# Servos.net
KiCad netlist of a schematic drawn in Altium Designer
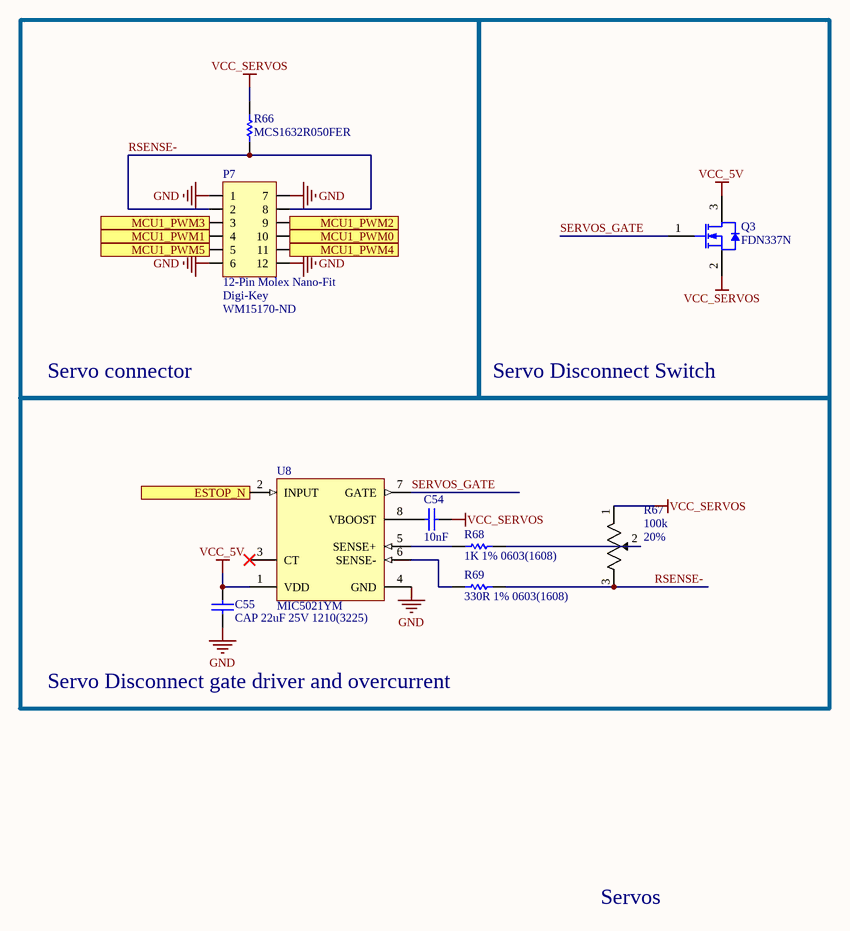
[diagram p0: Servos.SchDoc]

(export (version "E")
  (design (tool "Eeschema 10.0.6"))
  (components
    (comp (ref "C54")
      (value "10nF")
      (footprint "CAPC0603(1608)100_N")
      (description "CAP 10nF 25V ±2% 0603 (1608 Metric) Thickness 1mm SMD")
      (fields (field (name "TOLERANCE") "Â±2%"))
      (libsource (lib "Altium Content Vault") (part "CAP"))
    )
    (comp (ref "C55")
      (value "CAP 22uF 25V 1210(3225)")
      (footprint "CAPC1210(3225)220_N")
      (description "CAP 22uF 25V -20% to +80% 1210 (3225 Metric) Thickness 2.2mm SMD")
      (fields (field (name "TOLERANCE") "-20% to +80%"))
      (libsource (lib "Altium Content Vault") (part "CAP"))
    )
    (comp (ref "P7")
      (value "12-Pin Molex Nano-Fit")
      (footprint "MOLEX NANO-FIT 2X6 - Right Angle")
      (description "NanoFit RA Hdr TH DR 12Ckt")
      (fields (field (name "SUPPLIER 1") "Digi-Key") (field (name "SUPPLIER PART NUMBER 1") "WM15170-ND"))
      (libsource (lib "CMR_Connectors") (part "12-Pin 2-Row Nano-Fit"))
    )
    (comp (ref "Q3")
      (value "FDN337N")
      (footprint "FAIR-SSOT3L-3_V")
      (fields (field (name "MANUFACTURER") "Fairchild Semiconductor"))
      (libsource (lib "Altium Content Vault") (part "NEMOS-GSD-3"))
    )
    (comp (ref "R66")
      (value "MCS1632R050FER")
      (footprint "RESC3216X62X50LL20T20")
      (description "Chip Resistor, 0.05 Ohm, +/- 1%, 1 W, -55 to 155 degC, 1206 (3216 Metric), RoHS, Tape and Reel")
      (fields (field (name "TOLERANCE") "50ppm"))
      (libsource (lib "Altium Content Vault") (part "RES-2"))
    )
    (comp (ref "R67")
      (value "100k")
      (footprint "TT BI 22A TRIM POT")
      (description "TT Electronics BI 22AR100KLFTR SMT trim pot, 100k 20%")
      (fields (field (name "TOLERANCE") "20%") (field (name "Comment") "22AR100KLFTR"))
      (libsource (lib "CMR_Resistors_Capacitors_and_Inductors") (part "TT 22AR Trim Pot"))
    )
    (comp (ref "R68")
      (value "1K 1% 0603(1608)")
      (footprint "RESC0603(1608)_N")
      (description "1K 0.1W 1% 0603 (1608 Metric)  SMD")
      (fields (field (name "TOLERANCE") "1 %") (field (name "POWER") "0.1 W"))
      (libsource (lib "Altium Content Vault") (part "RES"))
    )
    (comp (ref "R69")
      (value "330R 1% 0603(1608)")
      (footprint "RESC0603(1608)_N")
      (description "330R 0.1W 1% 0603 (1608 Metric)  SMD")
      (fields (field (name "TOLERANCE") "1 %") (field (name "POWER") "0.1 W"))
      (libsource (lib "Altium Content Vault") (part "RES"))
    )
    (comp (ref "U8")
      (value "MIC5021YM")
      (footprint "MICL-SOICN-8LD-PL-1_V")
      (description "High-Speed High-Side MOSFET Driver, 12 to 36 V, -40 to 85 degC, 8-Pin SOIC, RoHS, Tube")
      (libsource (lib "Altium Content Vault") (part "MICL-MIC5021B_YM-8"))
    )
  )
  (nets
    (net (code "1") (name "/ESTOP_N") (class "Default")
      (node (ref "U8") (pin "2") (pinfunction "INPUT_2") (pintype "input"))
    )
    (net (code "2") (name "/MCU1_PWM0") (class "Default")
      (node (ref "P7") (pin "10") (pinfunction "10_10") (pintype "passive"))
    )
    (net (code "3") (name "/MCU1_PWM1") (class "Default")
      (node (ref "P7") (pin "4") (pinfunction "4_4") (pintype "passive"))
    )
    (net (code "4") (name "/MCU1_PWM2") (class "Default")
      (node (ref "P7") (pin "9") (pinfunction "9_9") (pintype "passive"))
    )
    (net (code "5") (name "/MCU1_PWM3") (class "Default")
      (node (ref "P7") (pin "3") (pinfunction "3_3") (pintype "passive"))
    )
    (net (code "6") (name "/MCU1_PWM4") (class "Default")
      (node (ref "P7") (pin "11") (pinfunction "11_11") (pintype "passive"))
    )
    (net (code "7") (name "/MCU1_PWM5") (class "Default")
      (node (ref "P7") (pin "5") (pinfunction "5_5") (pintype "passive"))
    )
    (net (code "8") (name "/RSENSE-") (class "Default")
      (node (ref "P7") (pin "2") (pinfunction "2_2") (pintype "passive"))
      (node (ref "P7") (pin "8") (pinfunction "8_8") (pintype "passive"))
      (node (ref "R66") (pin "1") (pinfunction "1_1") (pintype "passive"))
      (node (ref "R67") (pin "3") (pinfunction "3_3") (pintype "passive"))
      (node (ref "R69") (pin "2") (pinfunction "2_2") (pintype "passive"))
    )
    (net (code "9") (name "/SERVOS_GATE") (class "Default")
      (node (ref "Q3") (pin "1") (pinfunction "G_1") (pintype "passive"))
      (node (ref "U8") (pin "7") (pinfunction "GATE_7") (pintype "output"))
    )
    (net (code "10") (name "GND") (class "Default")
      (node (ref "C55") (pin "1") (pinfunction "1_1") (pintype "passive"))
      (node (ref "P7") (pin "1") (pinfunction "1_1") (pintype "passive"))
      (node (ref "P7") (pin "12") (pinfunction "12_12") (pintype "passive"))
      (node (ref "P7") (pin "6") (pinfunction "6_6") (pintype "passive"))
      (node (ref "P7") (pin "7") (pinfunction "7_7") (pintype "passive"))
      (node (ref "U8") (pin "4") (pinfunction "GND_4") (pintype "power_in"))
    )
    (net (code "11") (name "Net-(R67-Pad2)") (class "Default")
      (node (ref "R67") (pin "2") (pinfunction "2_2") (pintype "passive"))
      (node (ref "R68") (pin "2") (pinfunction "2_2") (pintype "passive"))
    )
    (net (code "12") (name "Net-(U8-SENSE+)") (class "Default")
      (node (ref "R68") (pin "1") (pinfunction "1_1") (pintype "passive"))
      (node (ref "U8") (pin "5") (pinfunction "SENSE+_5") (pintype "input"))
    )
    (net (code "13") (name "Net-(U8-SENSE-)") (class "Default")
      (node (ref "R69") (pin "1") (pinfunction "1_1") (pintype "passive"))
      (node (ref "U8") (pin "6") (pinfunction "SENSE-_6") (pintype "input"))
    )
    (net (code "14") (name "Net-(U8-VBOOST)") (class "Default")
      (node (ref "C54") (pin "1") (pinfunction "1_1") (pintype "passive"))
      (node (ref "U8") (pin "8") (pinfunction "VBOOST_8") (pintype "power_in"))
    )
    (net (code "15") (name "VCC_5V") (class "Default")
      (node (ref "C55") (pin "2") (pinfunction "2_2") (pintype "passive"))
      (node (ref "Q3") (pin "3") (pinfunction "D_3") (pintype "passive"))
      (node (ref "U8") (pin "1") (pinfunction "VDD_1") (pintype "power_in"))
    )
    (net (code "16") (name "VCC_SERVOS") (class "Default")
      (node (ref "C54") (pin "2") (pinfunction "2_2") (pintype "passive"))
      (node (ref "Q3") (pin "2") (pinfunction "S_2") (pintype "passive"))
      (node (ref "R66") (pin "2") (pinfunction "2_2") (pintype "passive"))
      (node (ref "R67") (pin "1") (pinfunction "1_1") (pintype "passive"))
    )
    (net (code "17") (name "unconnected-(U8-CT-Pad3)") (class "Default")
      (node (ref "U8") (pin "3") (pinfunction "CT_3") (pintype "passive+no_connect"))
    )
  )
)
